# analogControlBoardV1.net
KiCad netlist of a schematic drawn in EAGLE
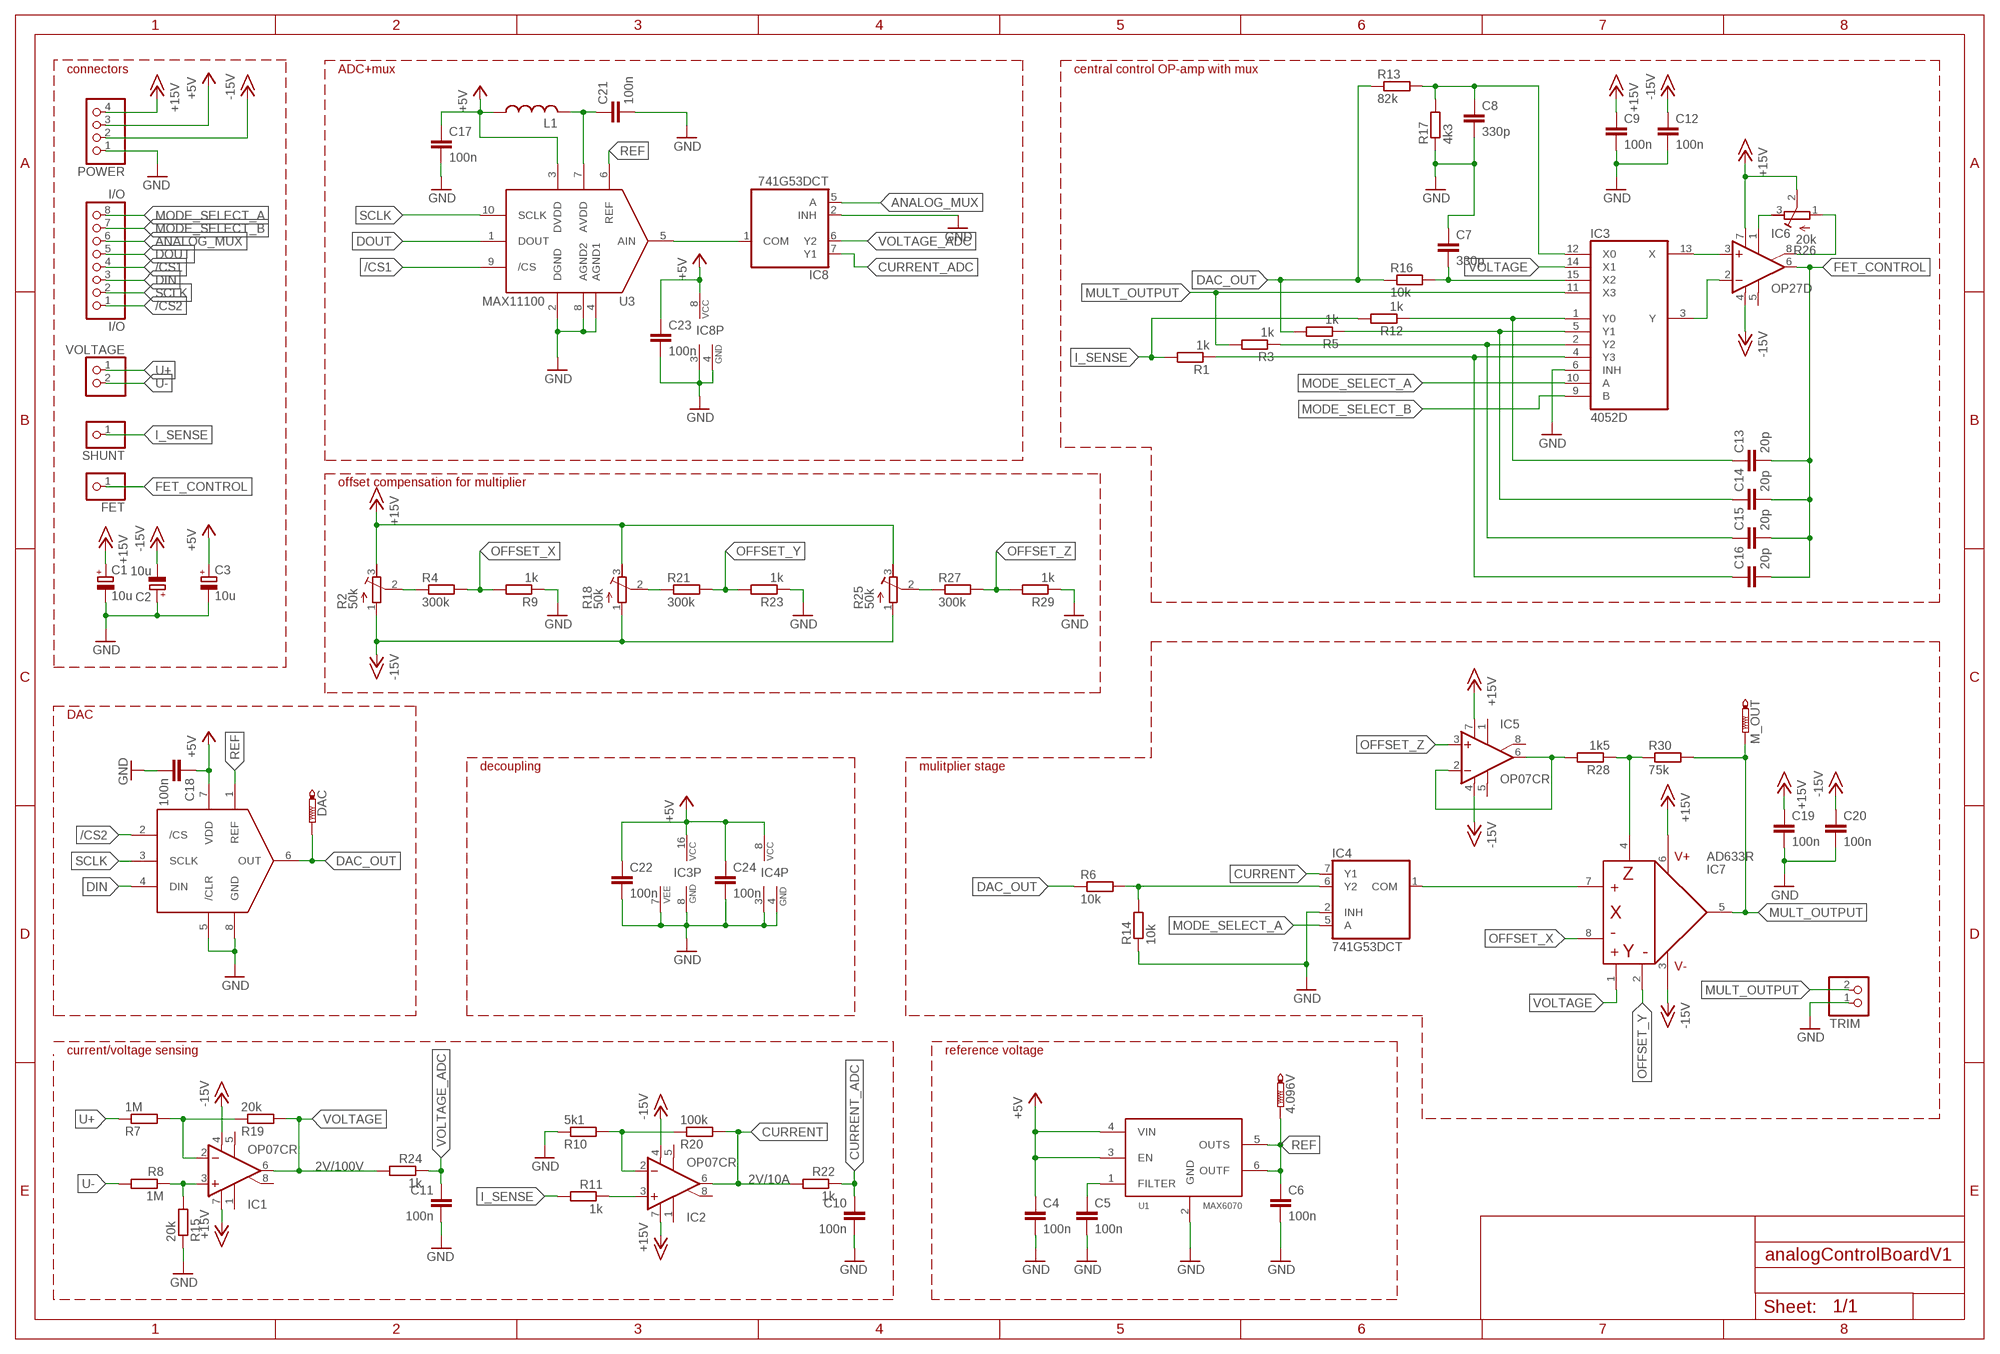
[diagram p0: schematic, sheet 1]

(export (version "E")
  (design (tool "Eeschema 10.0.6"))
  (components
    (comp (ref "4.096V")
      (value "PTR1TP06R")
      (footprint "eagle-import:TP06R")
      (libsource (lib "eagle-import") (part "PTR1TP06R"))
    )
    (comp (ref "C1")
      (value "10u")
      (footprint "eagle-import:153CLV-0505")
      (libsource (lib "eagle-import") (part "CPOL-EU153CLV-0505"))
    )
    (comp (ref "C2")
      (value "10u")
      (footprint "eagle-import:153CLV-0505")
      (libsource (lib "eagle-import") (part "CPOL-EU153CLV-0505"))
    )
    (comp (ref "C3")
      (value "10u")
      (footprint "eagle-import:153CLV-0505")
      (libsource (lib "eagle-import") (part "CPOL-EU153CLV-0505"))
    )
    (comp (ref "C4")
      (value "100n")
      (footprint "eagle-import:C0603K")
      (libsource (lib "eagle-import") (part "C-EUC0603K"))
    )
    (comp (ref "C5")
      (value "100n")
      (footprint "eagle-import:C0603K")
      (libsource (lib "eagle-import") (part "C-EUC0603K"))
    )
    (comp (ref "C6")
      (value "100n")
      (footprint "eagle-import:C0603K")
      (libsource (lib "eagle-import") (part "C-EUC0603K"))
    )
    (comp (ref "C7")
      (value "330p")
      (footprint "eagle-import:C0603K")
      (libsource (lib "eagle-import") (part "C-EUC0603K"))
    )
    (comp (ref "C8")
      (value "330p")
      (footprint "eagle-import:C0603K")
      (libsource (lib "eagle-import") (part "C-EUC0603K"))
    )
    (comp (ref "C9")
      (value "100n")
      (footprint "eagle-import:C0603K")
      (libsource (lib "eagle-import") (part "C-EUC0603K"))
    )
    (comp (ref "C10")
      (value "100n")
      (footprint "eagle-import:C0603K")
      (libsource (lib "eagle-import") (part "C-EUC0603K"))
    )
    (comp (ref "C11")
      (value "100n")
      (footprint "eagle-import:C0603K")
      (libsource (lib "eagle-import") (part "C-EUC0603K"))
    )
    (comp (ref "C12")
      (value "100n")
      (footprint "eagle-import:C0603K")
      (libsource (lib "eagle-import") (part "C-EUC0603K"))
    )
    (comp (ref "C13")
      (value "20p")
      (footprint "eagle-import:C0603K")
      (libsource (lib "eagle-import") (part "C-EUC0603K"))
    )
    (comp (ref "C14")
      (value "20p")
      (footprint "eagle-import:C0603K")
      (libsource (lib "eagle-import") (part "C-EUC0603K"))
    )
    (comp (ref "C15")
      (value "20p")
      (footprint "eagle-import:C0603K")
      (libsource (lib "eagle-import") (part "C-EUC0603K"))
    )
    (comp (ref "C16")
      (value "20p")
      (footprint "eagle-import:C0603K")
      (libsource (lib "eagle-import") (part "C-EUC0603K"))
    )
    (comp (ref "C17")
      (value "100n")
      (footprint "eagle-import:C0603K")
      (libsource (lib "eagle-import") (part "C-EUC0603K"))
    )
    (comp (ref "C18")
      (value "100n")
      (footprint "eagle-import:C0603K")
      (libsource (lib "eagle-import") (part "C-EUC0603K"))
    )
    (comp (ref "C19")
      (value "100n")
      (footprint "eagle-import:C0603K")
      (libsource (lib "eagle-import") (part "C-EUC0603K"))
    )
    (comp (ref "C20")
      (value "100n")
      (footprint "eagle-import:C0603K")
      (libsource (lib "eagle-import") (part "C-EUC0603K"))
    )
    (comp (ref "C21")
      (value "100n")
      (footprint "eagle-import:C0603K")
      (libsource (lib "eagle-import") (part "C-EUC0603K"))
    )
    (comp (ref "C22")
      (value "100n")
      (footprint "eagle-import:C0603K")
      (libsource (lib "eagle-import") (part "C-EUC0603K"))
    )
    (comp (ref "C23")
      (value "100n")
      (footprint "eagle-import:C0603K")
      (libsource (lib "eagle-import") (part "C-EUC0603K"))
    )
    (comp (ref "C24")
      (value "100n")
      (footprint "eagle-import:C0603K")
      (libsource (lib "eagle-import") (part "C-EUC0603K"))
    )
    (comp (ref "DAC")
      (value "PTR1TP06R")
      (footprint "eagle-import:TP06R")
      (libsource (lib "eagle-import") (part "PTR1TP06R"))
    )
    (comp (ref "FET")
      (value "PINHD-1X1")
      (footprint "eagle-import:1X01")
      (libsource (lib "eagle-import") (part "PINHD-1X1"))
    )
    (comp (ref "I/O")
      (value "I/O")
      (footprint "eagle-import:1X08")
      (libsource (lib "eagle-import") (part "PINHD-1X8"))
    )
    (comp (ref "IC1")
      (value "OP07CR")
      (footprint "eagle-import:SO08")
      (libsource (lib "eagle-import") (part "OP07RC"))
    )
    (comp (ref "IC2")
      (value "OP07CR")
      (footprint "eagle-import:SO08")
      (libsource (lib "eagle-import") (part "OP07RC"))
    )
    (comp (ref "IC3")
      (value "4052D")
      (footprint "eagle-import:SO16")
      (libsource (lib "eagle-import") (part "4052D"))
    )
    (comp (ref "IC4")
      (value "741G53DCT")
      (footprint "eagle-import:DCT_R-PDSO-G8")
      (libsource (lib "eagle-import") (part "741G53DCT"))
    )
    (comp (ref "IC5")
      (value "OP07CR")
      (footprint "eagle-import:SO08")
      (libsource (lib "eagle-import") (part "OP07RC"))
    )
    (comp (ref "IC6")
      (value "OP27D")
      (footprint "eagle-import:SO08")
      (libsource (lib "eagle-import") (part "OP27D"))
    )
    (comp (ref "IC7")
      (value "AD633R")
      (footprint "eagle-import:SO08")
      (libsource (lib "eagle-import") (part "AD633R"))
    )
    (comp (ref "IC8")
      (value "741G53DCT")
      (footprint "eagle-import:DCT_R-PDSO-G8")
      (libsource (lib "eagle-import") (part "741G53DCT"))
    )
    (comp (ref "L1")
      (value "INDUCTOR0603")
      (footprint "eagle-import:R0603")
      (libsource (lib "eagle-import") (part "INDUCTOR0603"))
    )
    (comp (ref "M_OUT")
      (value "PTR1TP06R")
      (footprint "eagle-import:TP06R")
      (libsource (lib "eagle-import") (part "PTR1TP06R"))
    )
    (comp (ref "POWER")
      (value "PINHD-1X4")
      (footprint "eagle-import:1X04")
      (libsource (lib "eagle-import") (part "PINHD-1X4"))
    )
    (comp (ref "R1")
      (value "1k")
      (footprint "eagle-import:R0603")
      (libsource (lib "eagle-import") (part "R-EU_R0603"))
    )
    (comp (ref "R2")
      (value "50k")
      (footprint "eagle-import:RTRIM64W")
      (libsource (lib "eagle-import") (part "R-TRIMM64W"))
    )
    (comp (ref "R3")
      (value "1k")
      (footprint "eagle-import:R0603")
      (libsource (lib "eagle-import") (part "R-EU_R0603"))
    )
    (comp (ref "R4")
      (value "300k")
      (footprint "eagle-import:R0603")
      (libsource (lib "eagle-import") (part "R-EU_R0603"))
    )
    (comp (ref "R5")
      (value "1k")
      (footprint "eagle-import:R0603")
      (libsource (lib "eagle-import") (part "R-EU_R0603"))
    )
    (comp (ref "R6")
      (value "10k")
      (footprint "eagle-import:R0603")
      (libsource (lib "eagle-import") (part "R-EU_R0603"))
    )
    (comp (ref "R7")
      (value "1M")
      (footprint "eagle-import:R0603")
      (libsource (lib "eagle-import") (part "R-EU_R0603"))
    )
    (comp (ref "R8")
      (value "1M")
      (footprint "eagle-import:R0603")
      (libsource (lib "eagle-import") (part "R-EU_R0603"))
    )
    (comp (ref "R9")
      (value "1k")
      (footprint "eagle-import:R0603")
      (libsource (lib "eagle-import") (part "R-EU_R0603"))
    )
    (comp (ref "R10")
      (value "5k1")
      (footprint "eagle-import:R0603")
      (libsource (lib "eagle-import") (part "R-EU_R0603"))
    )
    (comp (ref "R11")
      (value "1k")
      (footprint "eagle-import:R0603")
      (libsource (lib "eagle-import") (part "R-EU_R0603"))
    )
    (comp (ref "R12")
      (value "1k")
      (footprint "eagle-import:R0603")
      (libsource (lib "eagle-import") (part "R-EU_R0603"))
    )
    (comp (ref "R13")
      (value "82k")
      (footprint "eagle-import:R0603")
      (libsource (lib "eagle-import") (part "R-EU_R0603"))
    )
    (comp (ref "R14")
      (value "10k")
      (footprint "eagle-import:R0603")
      (libsource (lib "eagle-import") (part "R-EU_R0603"))
    )
    (comp (ref "R15")
      (value "20k")
      (footprint "eagle-import:R0603")
      (libsource (lib "eagle-import") (part "R-EU_R0603"))
    )
    (comp (ref "R16")
      (value "10k")
      (footprint "eagle-import:R0603")
      (libsource (lib "eagle-import") (part "R-EU_R0603"))
    )
    (comp (ref "R17")
      (value "4k3")
      (footprint "eagle-import:R0603")
      (libsource (lib "eagle-import") (part "R-EU_R0603"))
    )
    (comp (ref "R18")
      (value "50k")
      (footprint "eagle-import:RTRIM64W")
      (libsource (lib "eagle-import") (part "R-TRIMM64W"))
    )
    (comp (ref "R19")
      (value "20k")
      (footprint "eagle-import:R0603")
      (libsource (lib "eagle-import") (part "R-EU_R0603"))
    )
    (comp (ref "R20")
      (value "100k")
      (footprint "eagle-import:R0603")
      (libsource (lib "eagle-import") (part "R-EU_R0603"))
    )
    (comp (ref "R21")
      (value "300k")
      (footprint "eagle-import:R0603")
      (libsource (lib "eagle-import") (part "R-EU_R0603"))
    )
    (comp (ref "R22")
      (value "1k")
      (footprint "eagle-import:R0603")
      (libsource (lib "eagle-import") (part "R-EU_R0603"))
    )
    (comp (ref "R23")
      (value "1k")
      (footprint "eagle-import:R0603")
      (libsource (lib "eagle-import") (part "R-EU_R0603"))
    )
    (comp (ref "R24")
      (value "1k")
      (footprint "eagle-import:R0603")
      (libsource (lib "eagle-import") (part "R-EU_R0603"))
    )
    (comp (ref "R25")
      (value "50k")
      (footprint "eagle-import:RTRIM64W")
      (libsource (lib "eagle-import") (part "R-TRIMM64W"))
    )
    (comp (ref "R26")
      (value "20k")
      (footprint "eagle-import:RTRIM64W")
      (libsource (lib "eagle-import") (part "R-TRIMM64W"))
    )
    (comp (ref "R27")
      (value "300k")
      (footprint "eagle-import:R0603")
      (libsource (lib "eagle-import") (part "R-EU_R0603"))
    )
    (comp (ref "R28")
      (value "1k5")
      (footprint "eagle-import:R0603")
      (libsource (lib "eagle-import") (part "R-EU_R0603"))
    )
    (comp (ref "R29")
      (value "1k")
      (footprint "eagle-import:R0603")
      (libsource (lib "eagle-import") (part "R-EU_R0603"))
    )
    (comp (ref "R30")
      (value "75k")
      (footprint "eagle-import:R0603")
      (libsource (lib "eagle-import") (part "R-EU_R0603"))
    )
    (comp (ref "SHUNT")
      (value "PINHD-1X1")
      (footprint "eagle-import:1X01")
      (libsource (lib "eagle-import") (part "PINHD-1X1"))
    )
    (comp (ref "TRIM")
      (value "PINHD-1X2")
      (footprint "eagle-import:1X02")
      (libsource (lib "eagle-import") (part "PINHD-1X2"))
    )
    (comp (ref "U1")
      (value "MAX6070")
      (footprint "eagle-import:SOT23-6L")
      (libsource (lib "eagle-import") (part "MAX6070"))
    )
    (comp (ref "U2")
      (value "MAX5216")
      (footprint "eagle-import:UMAX8")
      (libsource (lib "eagle-import") (part "MAX5216"))
    )
    (comp (ref "U3")
      (value "MAX11100")
      (footprint "eagle-import:UMAX10")
      (libsource (lib "eagle-import") (part "MAX11100"))
    )
    (comp (ref "VOLTAGE")
      (value "PINHD-1X2")
      (footprint "eagle-import:1X02")
      (libsource (lib "eagle-import") (part "PINHD-1X2"))
    )
  )
  (nets
    (net (code "1") (name "+5V") (class "Default")
      (node (ref "C17") (pin "1") (pinfunction "1_1") (pintype "passive"))
      (node (ref "C18") (pin "1") (pinfunction "1_1") (pintype "passive"))
      (node (ref "C22") (pin "1") (pinfunction "1_1") (pintype "passive"))
      (node (ref "C23") (pin "1") (pinfunction "1_1") (pintype "passive"))
      (node (ref "C24") (pin "1") (pinfunction "1_1") (pintype "passive"))
      (node (ref "C3") (pin "+") (pinfunction "+_+") (pintype "passive"))
      (node (ref "C4") (pin "1") (pinfunction "1_1") (pintype "passive"))
      (node (ref "IC3") (pin "16") (pinfunction "VCC_16") (pintype "power_in"))
      (node (ref "IC4") (pin "8") (pinfunction "VCC_8") (pintype "power_in"))
      (node (ref "IC8") (pin "8") (pinfunction "VCC_8") (pintype "power_in"))
      (node (ref "L1") (pin "1") (pinfunction "1_1") (pintype "passive"))
      (node (ref "POWER") (pin "3") (pinfunction "3_3") (pintype "passive"))
      (node (ref "U1") (pin "3") (pinfunction "EN_3") (pintype "bidirectional"))
      (node (ref "U1") (pin "4") (pinfunction "VIN_4") (pintype "bidirectional"))
      (node (ref "U2") (pin "7") (pinfunction "VDD_7") (pintype "bidirectional"))
      (node (ref "U3") (pin "3") (pinfunction "DVDD_3") (pintype "bidirectional"))
    )
    (net (code "2") (name "+15V") (class "Default")
      (node (ref "C1") (pin "+") (pinfunction "+_+") (pintype "passive"))
      (node (ref "C19") (pin "1") (pinfunction "1_1") (pintype "passive"))
      (node (ref "C9") (pin "1") (pinfunction "1_1") (pintype "passive"))
      (node (ref "IC1") (pin "7") (pinfunction "V+_7") (pintype "power_in"))
      (node (ref "IC2") (pin "7") (pinfunction "V+_7") (pintype "power_in"))
      (node (ref "IC5") (pin "7") (pinfunction "V+_7") (pintype "power_in"))
      (node (ref "IC6") (pin "7") (pinfunction "V+_7") (pintype "power_in"))
      (node (ref "IC7") (pin "6") (pinfunction "V+_6") (pintype "power_in"))
      (node (ref "POWER") (pin "4") (pinfunction "4_4") (pintype "passive"))
      (node (ref "R18") (pin "3") (pinfunction "A_3") (pintype "passive"))
      (node (ref "R2") (pin "3") (pinfunction "A_3") (pintype "passive"))
      (node (ref "R25") (pin "3") (pinfunction "A_3") (pintype "passive"))
      (node (ref "R26") (pin "2") (pinfunction "S_2") (pintype "passive"))
    )
    (net (code "3") (name "-15V") (class "Default")
      (node (ref "C12") (pin "1") (pinfunction "1_1") (pintype "passive"))
      (node (ref "C2") (pin "-") (pinfunction "-_-") (pintype "passive"))
      (node (ref "C20") (pin "1") (pinfunction "1_1") (pintype "passive"))
      (node (ref "IC1") (pin "4") (pinfunction "V-_4") (pintype "power_in"))
      (node (ref "IC2") (pin "4") (pinfunction "V-_4") (pintype "power_in"))
      (node (ref "IC5") (pin "4") (pinfunction "V-_4") (pintype "power_in"))
      (node (ref "IC6") (pin "4") (pinfunction "V-_4") (pintype "power_in"))
      (node (ref "IC7") (pin "3") (pinfunction "V-_3") (pintype "power_in"))
      (node (ref "POWER") (pin "2") (pinfunction "2_2") (pintype "passive"))
      (node (ref "R18") (pin "1") (pinfunction "E_1") (pintype "passive"))
      (node (ref "R2") (pin "1") (pinfunction "E_1") (pintype "passive"))
      (node (ref "R25") (pin "1") (pinfunction "E_1") (pintype "passive"))
    )
    (net (code "4") (name "ANALOG_MUX") (class "Default")
      (node (ref "I/O") (pin "6") (pinfunction "6_6") (pintype "passive"))
      (node (ref "IC8") (pin "5") (pinfunction "A_5") (pintype "input"))
    )
    (net (code "5") (name "CURRENT") (class "Default")
      (node (ref "IC2") (pin "6") (pinfunction "OUT_6") (pintype "output"))
      (node (ref "IC4") (pin "7") (pinfunction "Y1_7") (pintype "bidirectional"))
      (node (ref "R20") (pin "2") (pinfunction "2_2") (pintype "passive"))
      (node (ref "R22") (pin "2") (pinfunction "2_2") (pintype "passive"))
    )
    (net (code "6") (name "CURRENT_ADC") (class "Default")
      (node (ref "C10") (pin "1") (pinfunction "1_1") (pintype "passive"))
      (node (ref "IC8") (pin "7") (pinfunction "Y1_7") (pintype "bidirectional"))
      (node (ref "R22") (pin "1") (pinfunction "1_1") (pintype "passive"))
    )
    (net (code "7") (name "DAC_OUT") (class "Default")
      (node (ref "DAC") (pin "TP") (pinfunction "TP_TP") (pintype "input"))
      (node (ref "R13") (pin "1") (pinfunction "1_1") (pintype "passive"))
      (node (ref "R16") (pin "1") (pinfunction "1_1") (pintype "passive"))
      (node (ref "R5") (pin "2") (pinfunction "2_2") (pintype "passive"))
      (node (ref "R6") (pin "1") (pinfunction "1_1") (pintype "passive"))
      (node (ref "U2") (pin "6") (pinfunction "OUT_6") (pintype "bidirectional"))
    )
    (net (code "8") (name "DIN") (class "Default")
      (node (ref "I/O") (pin "3") (pinfunction "3_3") (pintype "passive"))
      (node (ref "U2") (pin "4") (pinfunction "DIN_4") (pintype "bidirectional"))
    )
    (net (code "9") (name "DOUT") (class "Default")
      (node (ref "I/O") (pin "5") (pinfunction "5_5") (pintype "passive"))
      (node (ref "U3") (pin "1") (pinfunction "DOUT_1") (pintype "bidirectional"))
    )
    (net (code "10") (name "FET_CONTROL") (class "Default")
      (node (ref "C13") (pin "2") (pinfunction "2_2") (pintype "passive"))
      (node (ref "C14") (pin "2") (pinfunction "2_2") (pintype "passive"))
      (node (ref "C15") (pin "2") (pinfunction "2_2") (pintype "passive"))
      (node (ref "C16") (pin "2") (pinfunction "2_2") (pintype "passive"))
      (node (ref "FET") (pin "1") (pinfunction "1_1") (pintype "passive"))
      (node (ref "IC6") (pin "6") (pinfunction "OUT_6") (pintype "output"))
    )
    (net (code "11") (name "GND") (class "Default")
      (node (ref "C1") (pin "-") (pinfunction "-_-") (pintype "passive"))
      (node (ref "C10") (pin "2") (pinfunction "2_2") (pintype "passive"))
      (node (ref "C11") (pin "2") (pinfunction "2_2") (pintype "passive"))
      (node (ref "C12") (pin "2") (pinfunction "2_2") (pintype "passive"))
      (node (ref "C17") (pin "2") (pinfunction "2_2") (pintype "passive"))
      (node (ref "C18") (pin "2") (pinfunction "2_2") (pintype "passive"))
      (node (ref "C19") (pin "2") (pinfunction "2_2") (pintype "passive"))
      (node (ref "C2") (pin "+") (pinfunction "+_+") (pintype "passive"))
      (node (ref "C20") (pin "2") (pinfunction "2_2") (pintype "passive"))
      (node (ref "C21") (pin "2") (pinfunction "2_2") (pintype "passive"))
      (node (ref "C22") (pin "2") (pinfunction "2_2") (pintype "passive"))
      (node (ref "C23") (pin "2") (pinfunction "2_2") (pintype "passive"))
      (node (ref "C24") (pin "2") (pinfunction "2_2") (pintype "passive"))
      (node (ref "C3") (pin "-") (pinfunction "-_-") (pintype "passive"))
      (node (ref "C4") (pin "2") (pinfunction "2_2") (pintype "passive"))
      (node (ref "C5") (pin "2") (pinfunction "2_2") (pintype "passive"))
      (node (ref "C6") (pin "2") (pinfunction "2_2") (pintype "passive"))
      (node (ref "C7") (pin "1") (pinfunction "1_1") (pintype "passive"))
      (node (ref "C8") (pin "2") (pinfunction "2_2") (pintype "passive"))
      (node (ref "C9") (pin "2") (pinfunction "2_2") (pintype "passive"))
      (node (ref "IC3") (pin "6") (pinfunction "INH_6") (pintype "input"))
      (node (ref "IC3") (pin "7") (pinfunction "VEE_7") (pintype "power_in"))
      (node (ref "IC3") (pin "8") (pinfunction "GND_8") (pintype "power_in"))
      (node (ref "IC4") (pin "2") (pinfunction "INH_2") (pintype "input"))
      (node (ref "IC4") (pin "3") (pinfunction "GND_3") (pintype "power_in"))
      (node (ref "IC4") (pin "4") (pinfunction "GND_4") (pintype "power_in"))
      (node (ref "IC8") (pin "2") (pinfunction "INH_2") (pintype "input"))
      (node (ref "IC8") (pin "3") (pinfunction "GND_3") (pintype "power_in"))
      (node (ref "IC8") (pin "4") (pinfunction "GND_4") (pintype "power_in"))
      (node (ref "POWER") (pin "1") (pinfunction "1_1") (pintype "passive"))
      (node (ref "R10") (pin "1") (pinfunction "1_1") (pintype "passive"))
      (node (ref "R14") (pin "1") (pinfunction "1_1") (pintype "passive"))
      (node (ref "R15") (pin "1") (pinfunction "1_1") (pintype "passive"))
      (node (ref "R17") (pin "1") (pinfunction "1_1") (pintype "passive"))
      (node (ref "R23") (pin "1") (pinfunction "1_1") (pintype "passive"))
      (node (ref "R29") (pin "1") (pinfunction "1_1") (pintype "passive"))
      (node (ref "R9") (pin "1") (pinfunction "1_1") (pintype "passive"))
      (node (ref "TRIM") (pin "1") (pinfunction "1_1") (pintype "passive"))
      (node (ref "U1") (pin "2") (pinfunction "GND_2") (pintype "bidirectional"))
      (node (ref "U2") (pin "5") (pinfunction "/CLR_5") (pintype "bidirectional"))
      (node (ref "U2") (pin "8") (pinfunction "GND_8") (pintype "bidirectional"))
      (node (ref "U3") (pin "2") (pinfunction "DGND_2") (pintype "bidirectional"))
      (node (ref "U3") (pin "4") (pinfunction "AGND1_4") (pintype "bidirectional"))
      (node (ref "U3") (pin "8") (pinfunction "AGND2_8") (pintype "bidirectional"))
    )
    (net (code "12") (name "I_SENSE") (class "Default")
      (node (ref "R1") (pin "2") (pinfunction "2_2") (pintype "passive"))
      (node (ref "R11") (pin "2") (pinfunction "2_2") (pintype "passive"))
      (node (ref "R12") (pin "2") (pinfunction "2_2") (pintype "passive"))
      (node (ref "SHUNT") (pin "1") (pinfunction "1_1") (pintype "passive"))
    )
    (net (code "13") (name "MODE_SELECT_A") (class "Default")
      (node (ref "I/O") (pin "8") (pinfunction "8_8") (pintype "passive"))
      (node (ref "IC3") (pin "10") (pinfunction "A_10") (pintype "input"))
      (node (ref "IC4") (pin "5") (pinfunction "A_5") (pintype "input"))
    )
    (net (code "14") (name "MODE_SELECT_B") (class "Default")
      (node (ref "I/O") (pin "7") (pinfunction "7_7") (pintype "passive"))
      (node (ref "IC3") (pin "9") (pinfunction "B_9") (pintype "input"))
    )
    (net (code "15") (name "MULT_OUTPUT") (class "Default")
      (node (ref "IC3") (pin "11") (pinfunction "X3_11") (pintype "bidirectional"))
      (node (ref "IC7") (pin "5") (pinfunction "OUT_5") (pintype "bidirectional"))
      (node (ref "M_OUT") (pin "TP") (pinfunction "TP_TP") (pintype "input"))
      (node (ref "R3") (pin "2") (pinfunction "2_2") (pintype "passive"))
      (node (ref "R30") (pin "2") (pinfunction "2_2") (pintype "passive"))
      (node (ref "TRIM") (pin "2") (pinfunction "2_2") (pintype "passive"))
    )
    (net (code "16") (name "Net-(IC1-+IN)") (class "Default")
      (node (ref "IC1") (pin "3") (pinfunction "+IN_3") (pintype "input"))
      (node (ref "R15") (pin "2") (pinfunction "2_2") (pintype "passive"))
      (node (ref "R8") (pin "1") (pinfunction "1_1") (pintype "passive"))
    )
    (net (code "17") (name "Net-(IC1--IN)") (class "Default")
      (node (ref "IC1") (pin "2") (pinfunction "-IN_2") (pintype "input"))
      (node (ref "R19") (pin "1") (pinfunction "1_1") (pintype "passive"))
      (node (ref "R7") (pin "2") (pinfunction "2_2") (pintype "passive"))
    )
    (net (code "18") (name "Net-(IC2-+IN)") (class "Default")
      (node (ref "IC2") (pin "3") (pinfunction "+IN_3") (pintype "input"))
      (node (ref "R11") (pin "1") (pinfunction "1_1") (pintype "passive"))
    )
    (net (code "19") (name "Net-(IC2--IN)") (class "Default")
      (node (ref "IC2") (pin "2") (pinfunction "-IN_2") (pintype "input"))
      (node (ref "R10") (pin "2") (pinfunction "2_2") (pintype "passive"))
      (node (ref "R20") (pin "1") (pinfunction "1_1") (pintype "passive"))
    )
    (net (code "20") (name "Net-(IC3A-X)") (class "Default")
      (node (ref "IC3") (pin "13") (pinfunction "X_13") (pintype "bidirectional"))
      (node (ref "IC6") (pin "3") (pinfunction "+IN_3") (pintype "input"))
    )
    (net (code "21") (name "Net-(IC3A-X0)") (class "Default")
      (node (ref "C8") (pin "1") (pinfunction "1_1") (pintype "passive"))
      (node (ref "IC3") (pin "12") (pinfunction "X0_12") (pintype "bidirectional"))
      (node (ref "R13") (pin "2") (pinfunction "2_2") (pintype "passive"))
      (node (ref "R17") (pin "2") (pinfunction "2_2") (pintype "passive"))
    )
    (net (code "22") (name "Net-(IC3A-X2)") (class "Default")
      (node (ref "C7") (pin "2") (pinfunction "2_2") (pintype "passive"))
      (node (ref "IC3") (pin "15") (pinfunction "X2_15") (pintype "bidirectional"))
      (node (ref "R16") (pin "2") (pinfunction "2_2") (pintype "passive"))
    )
    (net (code "23") (name "Net-(IC3A-Y)") (class "Default")
      (node (ref "IC3") (pin "3") (pinfunction "Y_3") (pintype "bidirectional"))
      (node (ref "IC6") (pin "2") (pinfunction "-IN_2") (pintype "input"))
    )
    (net (code "24") (name "Net-(IC3A-Y0)") (class "Default")
      (node (ref "C13") (pin "1") (pinfunction "1_1") (pintype "passive"))
      (node (ref "IC3") (pin "1") (pinfunction "Y0_1") (pintype "bidirectional"))
      (node (ref "R12") (pin "1") (pinfunction "1_1") (pintype "passive"))
    )
    (net (code "25") (name "Net-(IC3A-Y1)") (class "Default")
      (node (ref "C14") (pin "1") (pinfunction "1_1") (pintype "passive"))
      (node (ref "IC3") (pin "5") (pinfunction "Y1_5") (pintype "bidirectional"))
      (node (ref "R5") (pin "1") (pinfunction "1_1") (pintype "passive"))
    )
    (net (code "26") (name "Net-(IC3A-Y2)") (class "Default")
      (node (ref "C15") (pin "1") (pinfunction "1_1") (pintype "passive"))
      (node (ref "IC3") (pin "2") (pinfunction "Y2_2") (pintype "bidirectional"))
      (node (ref "R3") (pin "1") (pinfunction "1_1") (pintype "passive"))
    )
    (net (code "27") (name "Net-(IC3A-Y3)") (class "Default")
      (node (ref "C16") (pin "1") (pinfunction "1_1") (pintype "passive"))
      (node (ref "IC3") (pin "4") (pinfunction "Y3_4") (pintype "bidirectional"))
      (node (ref "R1") (pin "1") (pinfunction "1_1") (pintype "passive"))
    )
    (net (code "28") (name "Net-(IC4A-COM)") (class "Default")
      (node (ref "IC4") (pin "1") (pinfunction "COM_1") (pintype "bidirectional"))
      (node (ref "IC7") (pin "7") (pinfunction "X+_7") (pintype "bidirectional"))
    )
    (net (code "29") (name "Net-(IC4A-Y2)") (class "Default")
      (node (ref "IC4") (pin "6") (pinfunction "Y2_6") (pintype "bidirectional"))
      (node (ref "R14") (pin "2") (pinfunction "2_2") (pintype "passive"))
      (node (ref "R6") (pin "2") (pinfunction "2_2") (pintype "passive"))
    )
    (net (code "30") (name "Net-(IC5--IN)") (class "Default")
      (node (ref "IC5") (pin "2") (pinfunction "-IN_2") (pintype "input"))
      (node (ref "IC5") (pin "6") (pinfunction "OUT_6") (pintype "output"))
      (node (ref "R28") (pin "2") (pinfunction "2_2") (pintype "passive"))
    )
    (net (code "31") (name "Net-(IC6-ON1)") (class "Default")
      (node (ref "IC6") (pin "1") (pinfunction "ON1_1") (pintype "passive"))
      (node (ref "R26") (pin "3") (pinfunction "A_3") (pintype "passive"))
    )
    (net (code "32") (name "Net-(IC6-ON2)") (class "Default")
      (node (ref "IC6") (pin "8") (pinfunction "ON2_8") (pintype "passive"))
      (node (ref "R26") (pin "1") (pinfunction "E_1") (pintype "passive"))
    )
    (net (code "33") (name "Net-(IC7-Z)") (class "Default")
      (node (ref "IC7") (pin "4") (pinfunction "Z_4") (pintype "bidirectional"))
      (node (ref "R28") (pin "1") (pinfunction "1_1") (pintype "passive"))
      (node (ref "R30") (pin "1") (pinfunction "1_1") (pintype "passive"))
    )
    (net (code "34") (name "Net-(IC8A-COM)") (class "Default")
      (node (ref "IC8") (pin "1") (pinfunction "COM_1") (pintype "bidirectional"))
      (node (ref "U3") (pin "5") (pinfunction "AIN_5") (pintype "bidirectional"))
    )
    (net (code "35") (name "Net-(R2-S)") (class "Default")
      (node (ref "R2") (pin "2") (pinfunction "S_2") (pintype "passive"))
      (node (ref "R4") (pin "1") (pinfunction "1_1") (pintype "passive"))
    )
    (net (code "36") (name "Net-(R18-S)") (class "Default")
      (node (ref "R18") (pin "2") (pinfunction "S_2") (pintype "passive"))
      (node (ref "R21") (pin "1") (pinfunction "1_1") (pintype "passive"))
    )
    (net (code "37") (name "Net-(R25-S)") (class "Default")
      (node (ref "R25") (pin "2") (pinfunction "S_2") (pintype "passive"))
      (node (ref "R27") (pin "1") (pinfunction "1_1") (pintype "passive"))
    )
    (net (code "38") (name "Net-(U1-FILTER)") (class "Default")
      (node (ref "C5") (pin "1") (pinfunction "1_1") (pintype "passive"))
      (node (ref "U1") (pin "1") (pinfunction "FILTER_1") (pintype "bidirectional"))
    )
    (net (code "39") (name "Net-(U3-AVDD)") (class "Default")
      (node (ref "C21") (pin "1") (pinfunction "1_1") (pintype "passive"))
      (node (ref "L1") (pin "2") (pinfunction "2_2") (pintype "passive"))
      (node (ref "U3") (pin "7") (pinfunction "AVDD_7") (pintype "bidirectional"))
    )
    (net (code "40") (name "OFFSET_X") (class "Default")
      (node (ref "IC7") (pin "8") (pinfunction "X-_8") (pintype "bidirectional"))
      (node (ref "R4") (pin "2") (pinfunction "2_2") (pintype "passive"))
      (node (ref "R9") (pin "2") (pinfunction "2_2") (pintype "passive"))
    )
    (net (code "41") (name "OFFSET_Y") (class "Default")
      (node (ref "IC7") (pin "2") (pinfunction "Y-_2") (pintype "bidirectional"))
      (node (ref "R21") (pin "2") (pinfunction "2_2") (pintype "passive"))
      (node (ref "R23") (pin "2") (pinfunction "2_2") (pintype "passive"))
    )
    (net (code "42") (name "OFFSET_Z") (class "Default")
      (node (ref "IC5") (pin "3") (pinfunction "+IN_3") (pintype "input"))
      (node (ref "R27") (pin "2") (pinfunction "2_2") (pintype "passive"))
      (node (ref "R29") (pin "2") (pinfunction "2_2") (pintype "passive"))
    )
    (net (code "43") (name "REF") (class "Default")
      (node (ref "4.096V") (pin "TP") (pinfunction "TP_TP") (pintype "input"))
      (node (ref "C6") (pin "1") (pinfunction "1_1") (pintype "passive"))
      (node (ref "U1") (pin "5") (pinfunction "OUTS_5") (pintype "bidirectional"))
      (node (ref "U1") (pin "6") (pinfunction "OUTF_6") (pintype "bidirectional"))
      (node (ref "U2") (pin "1") (pinfunction "REF_1") (pintype "bidirectional"))
      (node (ref "U3") (pin "6") (pinfunction "REF_6") (pintype "bidirectional"))
    )
    (net (code "44") (name "SCLK") (class "Default")
      (node (ref "I/O") (pin "2") (pinfunction "2_2") (pintype "passive"))
      (node (ref "U2") (pin "3") (pinfunction "SCLK_3") (pintype "bidirectional"))
      (node (ref "U3") (pin "10") (pinfunction "SCLK_10") (pintype "bidirectional"))
    )
    (net (code "45") (name "U+") (class "Default")
      (node (ref "R7") (pin "1") (pinfunction "1_1") (pintype "passive"))
      (node (ref "VOLTAGE") (pin "1") (pinfunction "1_1") (pintype "passive"))
    )
    (net (code "46") (name "U-") (class "Default")
      (node (ref "R8") (pin "2") (pinfunction "2_2") (pintype "passive"))
      (node (ref "VOLTAGE") (pin "2") (pinfunction "2_2") (pintype "passive"))
    )
    (net (code "47") (name "VOLTAGE") (class "Default")
      (node (ref "IC1") (pin "6") (pinfunction "OUT_6") (pintype "output"))
      (node (ref "IC3") (pin "14") (pinfunction "X1_14") (pintype "bidirectional"))
      (node (ref "IC7") (pin "1") (pinfunction "Y+_1") (pintype "bidirectional"))
      (node (ref "R19") (pin "2") (pinfunction "2_2") (pintype "passive"))
      (node (ref "R24") (pin "2") (pinfunction "2_2") (pintype "passive"))
    )
    (net (code "48") (name "VOLTAGE_ADC") (class "Default")
      (node (ref "C11") (pin "1") (pinfunction "1_1") (pintype "passive"))
      (node (ref "IC8") (pin "6") (pinfunction "Y2_6") (pintype "bidirectional"))
      (node (ref "R24") (pin "1") (pinfunction "1_1") (pintype "passive"))
    )
    (net (code "49") (name "unconnected-(IC1-ON1-Pad1)") (class "Default")
      (node (ref "IC1") (pin "1") (pinfunction "ON1_1") (pintype "passive"))
    )
    (net (code "50") (name "unconnected-(IC1-ON2-Pad8)") (class "Default")
      (node (ref "IC1") (pin "8") (pinfunction "ON2_8") (pintype "passive"))
    )
    (net (code "51") (name "unconnected-(IC1-OPT-Pad5)") (class "Default")
      (node (ref "IC1") (pin "5") (pinfunction "OPT_5") (pintype "passive"))
    )
    (net (code "52") (name "unconnected-(IC2-ON1-Pad1)") (class "Default")
      (node (ref "IC2") (pin "1") (pinfunction "ON1_1") (pintype "passive"))
    )
    (net (code "53") (name "unconnected-(IC2-ON2-Pad8)") (class "Default")
      (node (ref "IC2") (pin "8") (pinfunction "ON2_8") (pintype "passive"))
    )
    (net (code "54") (name "unconnected-(IC2-OPT-Pad5)") (class "Default")
      (node (ref "IC2") (pin "5") (pinfunction "OPT_5") (pintype "passive"))
    )
    (net (code "55") (name "unconnected-(IC5-ON1-Pad1)") (class "Default")
      (node (ref "IC5") (pin "1") (pinfunction "ON1_1") (pintype "passive"))
    )
    (net (code "56") (name "unconnected-(IC5-ON2-Pad8)") (class "Default")
      (node (ref "IC5") (pin "8") (pinfunction "ON2_8") (pintype "passive"))
    )
    (net (code "57") (name "unconnected-(IC5-OPT-Pad5)") (class "Default")
      (node (ref "IC5") (pin "5") (pinfunction "OPT_5") (pintype "passive"))
    )
    (net (code "58") (name "unconnected-(IC6-OPT-Pad5)") (class "Default")
      (node (ref "IC6") (pin "5") (pinfunction "OPT_5") (pintype "passive"))
    )
    (net (code "59") (name "{slash}CS1") (class "Default")
      (node (ref "I/O") (pin "4") (pinfunction "4_4") (pintype "passive"))
      (node (ref "U3") (pin "9") (pinfunction "/CS_9") (pintype "bidirectional"))
    )
    (net (code "60") (name "{slash}CS2") (class "Default")
      (node (ref "I/O") (pin "1") (pinfunction "1_1") (pintype "passive"))
      (node (ref "U2") (pin "2") (pinfunction "/CS_2") (pintype "bidirectional"))
    )
  )
)
